# RG191-M2_Header.net
KiCad netlist of a schematic drawn in Altium Designer
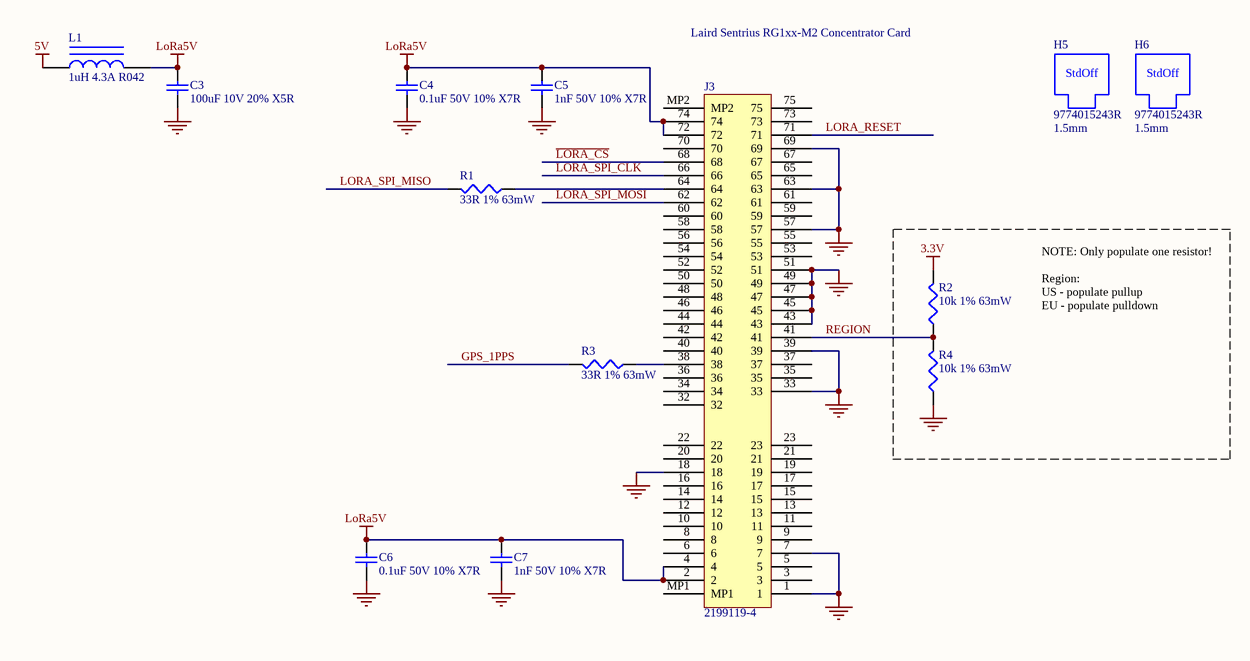
[diagram p0: RG191-M2 Header.SchDoc]

(export (version "E")
  (design (tool "Eeschema 10.0.6"))
  (components
    (comp (ref "C3")
      (value "100uF 10V 20% X5R")
      (footprint "C1210_L")
      (description "Capacitor")
      (libsource (lib "Miscellaneous Devices") (part "Cap"))
    )
    (comp (ref "C4")
      (value "0.1uF 50V 10% X7R")
      (footprint "CAPC1005L")
      (description "Capacitor")
      (libsource (lib "Miscellaneous Devices") (part "Cap"))
    )
    (comp (ref "C5")
      (value "1nF 50V 10% X7R")
      (footprint "CAPC1005L")
      (description "Capacitor")
      (libsource (lib "Miscellaneous Devices") (part "Cap"))
    )
    (comp (ref "C6")
      (value "0.1uF 50V 10% X7R")
      (footprint "CAPC1005L")
      (description "Capacitor")
      (libsource (lib "Miscellaneous Devices") (part "Cap"))
    )
    (comp (ref "C7")
      (value "1nF 50V 10% X7R")
      (footprint "CAPC1005L")
      (description "Capacitor")
      (libsource (lib "Miscellaneous Devices") (part "Cap"))
    )
    (comp (ref "H5")
      (value "9774015243R")
      (footprint "Wurth 9774015243R")
      (description "RND STANDOFF M2X0.4 STEEL")
      (fields (field (name "MANUFACTURER") "Wurth Electronics Inc") (field (name "HEIGHT") "1.5mm"))
      (libsource (lib "Latium Component Library") (part "SMD 1.5mm Spacer"))
    )
    (comp (ref "H6")
      (value "9774015243R")
      (footprint "Wurth 9774015243R")
      (description "RND STANDOFF M2X0.4 STEEL")
      (fields (field (name "MANUFACTURER") "Wurth Electronics Inc") (field (name "HEIGHT") "1.5mm"))
      (libsource (lib "Latium Component Library") (part "SMD 1.5mm Spacer"))
    )
    (comp (ref "J3")
      (value "2199119-4")
      (footprint "TE 2199119-4")
      (description "CONN FEMALE 67POS 0.020 GOLD")
      (fields (field (name "MANUFACTURER") "TE Connectivity AMP Connectors"))
      (libsource (lib "Latium Component Library") (part "TE2199119-4"))
    )
    (comp (ref "L1")
      (value "1uH 4.3A R042")
      (footprint "WE-LQS 252012")
      (description "FIXED IND 1UH 4.3A 42 MOHM SMD")
      (fields
        (field (name "MANUFACTURER PART NUMBER") "DFE252012P-1R0M=P2")
        (field (name "MANUFACTURER") "Murata Electronics")
      )
      (libsource (lib "Miscellaneous Devices") (part "Inductor Iron"))
    )
    (comp (ref "R1")
      (value "33R 1% 63mW")
      (footprint "RESC1005L")
      (description "Resistor")
      (libsource (lib "Miscellaneous Devices") (part "Res3"))
    )
    (comp (ref "R2")
      (value "10k 1% 63mW")
      (footprint "RESC1005L")
      (description "Resistor")
      (libsource (lib "Miscellaneous Devices") (part "Res3"))
    )
    (comp (ref "R3")
      (value "33R 1% 63mW")
      (footprint "RESC1005L")
      (description "Resistor")
      (libsource (lib "Miscellaneous Devices") (part "Res3"))
    )
    (comp (ref "R4")
      (value "10k 1% 63mW")
      (footprint "RESC1005L")
      (description "Resistor")
      (libsource (lib "Miscellaneous Devices") (part "Res3"))
    )
  )
  (nets
    (net (code "1") (name "/GPS_1PPS") (class "Default")
      (node (ref "R3") (pin "2") (pinfunction "2_2") (pintype "passive"))
    )
    (net (code "2") (name "/LORA_RESET") (class "Default")
      (node (ref "J3") (pin "71") (pinfunction "71_71") (pintype "passive"))
    )
    (net (code "3") (name "/LORA_SPI_CLK") (class "Default")
      (node (ref "J3") (pin "66") (pinfunction "66_66") (pintype "passive"))
    )
    (net (code "4") (name "/LORA_SPI_MISO") (class "Default")
      (node (ref "R1") (pin "2") (pinfunction "2_2") (pintype "passive"))
    )
    (net (code "5") (name "/LORA_SPI_MOSI") (class "Default")
      (node (ref "J3") (pin "62") (pinfunction "62_62") (pintype "passive"))
    )
    (net (code "6") (name "/REGION") (class "Default")
      (node (ref "J3") (pin "41") (pinfunction "41_41") (pintype "passive"))
      (node (ref "R2") (pin "1") (pinfunction "1_1") (pintype "passive"))
      (node (ref "R4") (pin "2") (pinfunction "2_2") (pintype "passive"))
    )
    (net (code "7") (name "/~{LORA_CS}") (class "Default")
      (node (ref "J3") (pin "68") (pinfunction "68_68") (pintype "passive"))
    )
    (net (code "8") (name "3.3V") (class "Default")
      (node (ref "R2") (pin "2") (pinfunction "2_2") (pintype "passive"))
    )
    (net (code "9") (name "5V") (class "Default")
      (node (ref "L1") (pin "1") (pinfunction "1_1") (pintype "passive"))
    )
    (net (code "10") (name "GND") (class "Default")
      (node (ref "C3") (pin "1") (pinfunction "1_1") (pintype "passive"))
      (node (ref "C4") (pin "2") (pinfunction "2_2") (pintype "passive"))
      (node (ref "C5") (pin "2") (pinfunction "2_2") (pintype "passive"))
      (node (ref "C6") (pin "2") (pinfunction "2_2") (pintype "passive"))
      (node (ref "C7") (pin "2") (pinfunction "2_2") (pintype "passive"))
      (node (ref "J3") (pin "1") (pinfunction "1_1") (pintype "passive"))
      (node (ref "J3") (pin "18") (pinfunction "18_18") (pintype "passive"))
      (node (ref "J3") (pin "33") (pinfunction "33_33") (pintype "passive"))
      (node (ref "J3") (pin "39") (pinfunction "39_39") (pintype "passive"))
      (node (ref "J3") (pin "43") (pinfunction "43_43") (pintype "passive"))
      (node (ref "J3") (pin "45") (pinfunction "45_45") (pintype "passive"))
      (node (ref "J3") (pin "47") (pinfunction "47_47") (pintype "passive"))
      (node (ref "J3") (pin "49") (pinfunction "49_49") (pintype "passive"))
      (node (ref "J3") (pin "51") (pinfunction "51_51") (pintype "passive"))
      (node (ref "J3") (pin "57") (pinfunction "57_57") (pintype "passive"))
      (node (ref "J3") (pin "63") (pinfunction "63_63") (pintype "passive"))
      (node (ref "J3") (pin "69") (pinfunction "69_69") (pintype "passive"))
      (node (ref "J3") (pin "7") (pinfunction "7_7") (pintype "passive"))
      (node (ref "R4") (pin "1") (pinfunction "1_1") (pintype "passive"))
    )
    (net (code "11") (name "LoRa5V") (class "Default")
      (node (ref "C3") (pin "2") (pinfunction "2_2") (pintype "passive"))
      (node (ref "C4") (pin "1") (pinfunction "1_1") (pintype "passive"))
      (node (ref "C5") (pin "1") (pinfunction "1_1") (pintype "passive"))
      (node (ref "C6") (pin "1") (pinfunction "1_1") (pintype "passive"))
      (node (ref "C7") (pin "1") (pinfunction "1_1") (pintype "passive"))
      (node (ref "J3") (pin "2") (pinfunction "2_2") (pintype "passive"))
      (node (ref "J3") (pin "4") (pinfunction "4_4") (pintype "passive"))
      (node (ref "J3") (pin "72") (pinfunction "72_72") (pintype "passive"))
      (node (ref "J3") (pin "74") (pinfunction "74_74") (pintype "passive"))
      (node (ref "L1") (pin "2") (pinfunction "2_2") (pintype "passive"))
    )
    (net (code "12") (name "Net-(J3-Pad38)") (class "Default")
      (node (ref "J3") (pin "38") (pinfunction "38_38") (pintype "passive"))
      (node (ref "R3") (pin "1") (pinfunction "1_1") (pintype "passive"))
    )
    (net (code "13") (name "Net-(J3-Pad64)") (class "Default")
      (node (ref "J3") (pin "64") (pinfunction "64_64") (pintype "passive"))
      (node (ref "R1") (pin "1") (pinfunction "1_1") (pintype "passive"))
    )
    (net (code "14") (name "unconnected-(J3-Pad3)") (class "Default")
      (node (ref "J3") (pin "3") (pinfunction "3_3") (pintype "passive"))
    )
    (net (code "15") (name "unconnected-(J3-Pad5)") (class "Default")
      (node (ref "J3") (pin "5") (pinfunction "5_5") (pintype "passive"))
    )
    (net (code "16") (name "unconnected-(J3-Pad6)") (class "Default")
      (node (ref "J3") (pin "6") (pinfunction "6_6") (pintype "passive"))
    )
    (net (code "17") (name "unconnected-(J3-Pad8)") (class "Default")
      (node (ref "J3") (pin "8") (pinfunction "8_8") (pintype "passive"))
    )
    (net (code "18") (name "unconnected-(J3-Pad9)") (class "Default")
      (node (ref "J3") (pin "9") (pinfunction "9_9") (pintype "passive"))
    )
    (net (code "19") (name "unconnected-(J3-Pad10)") (class "Default")
      (node (ref "J3") (pin "10") (pinfunction "10_10") (pintype "passive"))
    )
    (net (code "20") (name "unconnected-(J3-Pad11)") (class "Default")
      (node (ref "J3") (pin "11") (pinfunction "11_11") (pintype "passive"))
    )
    (net (code "21") (name "unconnected-(J3-Pad12)") (class "Default")
      (node (ref "J3") (pin "12") (pinfunction "12_12") (pintype "passive"))
    )
    (net (code "22") (name "unconnected-(J3-Pad13)") (class "Default")
      (node (ref "J3") (pin "13") (pinfunction "13_13") (pintype "passive"))
    )
    (net (code "23") (name "unconnected-(J3-Pad14)") (class "Default")
      (node (ref "J3") (pin "14") (pinfunction "14_14") (pintype "passive"))
    )
    (net (code "24") (name "unconnected-(J3-Pad15)") (class "Default")
      (node (ref "J3") (pin "15") (pinfunction "15_15") (pintype "passive"))
    )
    (net (code "25") (name "unconnected-(J3-Pad16)") (class "Default")
      (node (ref "J3") (pin "16") (pinfunction "16_16") (pintype "passive"))
    )
    (net (code "26") (name "unconnected-(J3-Pad17)") (class "Default")
      (node (ref "J3") (pin "17") (pinfunction "17_17") (pintype "passive"))
    )
    (net (code "27") (name "unconnected-(J3-Pad19)") (class "Default")
      (node (ref "J3") (pin "19") (pinfunction "19_19") (pintype "passive"))
    )
    (net (code "28") (name "unconnected-(J3-Pad20)") (class "Default")
      (node (ref "J3") (pin "20") (pinfunction "20_20") (pintype "passive"))
    )
    (net (code "29") (name "unconnected-(J3-Pad21)") (class "Default")
      (node (ref "J3") (pin "21") (pinfunction "21_21") (pintype "passive"))
    )
    (net (code "30") (name "unconnected-(J3-Pad22)") (class "Default")
      (node (ref "J3") (pin "22") (pinfunction "22_22") (pintype "passive"))
    )
    (net (code "31") (name "unconnected-(J3-Pad23)") (class "Default")
      (node (ref "J3") (pin "23") (pinfunction "23_23") (pintype "passive"))
    )
    (net (code "32") (name "unconnected-(J3-Pad32)") (class "Default")
      (node (ref "J3") (pin "32") (pinfunction "32_32") (pintype "passive"))
    )
    (net (code "33") (name "unconnected-(J3-Pad34)") (class "Default")
      (node (ref "J3") (pin "34") (pinfunction "34_34") (pintype "passive"))
    )
    (net (code "34") (name "unconnected-(J3-Pad35)") (class "Default")
      (node (ref "J3") (pin "35") (pinfunction "35_35") (pintype "passive"))
    )
    (net (code "35") (name "unconnected-(J3-Pad36)") (class "Default")
      (node (ref "J3") (pin "36") (pinfunction "36_36") (pintype "passive"))
    )
    (net (code "36") (name "unconnected-(J3-Pad37)") (class "Default")
      (node (ref "J3") (pin "37") (pinfunction "37_37") (pintype "passive"))
    )
    (net (code "37") (name "unconnected-(J3-Pad40)") (class "Default")
      (node (ref "J3") (pin "40") (pinfunction "40_40") (pintype "passive"))
    )
    (net (code "38") (name "unconnected-(J3-Pad42)") (class "Default")
      (node (ref "J3") (pin "42") (pinfunction "42_42") (pintype "passive"))
    )
    (net (code "39") (name "unconnected-(J3-Pad44)") (class "Default")
      (node (ref "J3") (pin "44") (pinfunction "44_44") (pintype "passive"))
    )
    (net (code "40") (name "unconnected-(J3-Pad46)") (class "Default")
      (node (ref "J3") (pin "46") (pinfunction "46_46") (pintype "passive"))
    )
    (net (code "41") (name "unconnected-(J3-Pad48)") (class "Default")
      (node (ref "J3") (pin "48") (pinfunction "48_48") (pintype "passive"))
    )
    (net (code "42") (name "unconnected-(J3-Pad50)") (class "Default")
      (node (ref "J3") (pin "50") (pinfunction "50_50") (pintype "passive"))
    )
    (net (code "43") (name "unconnected-(J3-Pad52)") (class "Default")
      (node (ref "J3") (pin "52") (pinfunction "52_52") (pintype "passive"))
    )
    (net (code "44") (name "unconnected-(J3-Pad53)") (class "Default")
      (node (ref "J3") (pin "53") (pinfunction "53_53") (pintype "passive"))
    )
    (net (code "45") (name "unconnected-(J3-Pad54)") (class "Default")
      (node (ref "J3") (pin "54") (pinfunction "54_54") (pintype "passive"))
    )
    (net (code "46") (name "unconnected-(J3-Pad55)") (class "Default")
      (node (ref "J3") (pin "55") (pinfunction "55_55") (pintype "passive"))
    )
    (net (code "47") (name "unconnected-(J3-Pad56)") (class "Default")
      (node (ref "J3") (pin "56") (pinfunction "56_56") (pintype "passive"))
    )
    (net (code "48") (name "unconnected-(J3-Pad58)") (class "Default")
      (node (ref "J3") (pin "58") (pinfunction "58_58") (pintype "passive"))
    )
    (net (code "49") (name "unconnected-(J3-Pad59)") (class "Default")
      (node (ref "J3") (pin "59") (pinfunction "59_59") (pintype "passive"))
    )
    (net (code "50") (name "unconnected-(J3-Pad60)") (class "Default")
      (node (ref "J3") (pin "60") (pinfunction "60_60") (pintype "passive"))
    )
    (net (code "51") (name "unconnected-(J3-Pad61)") (class "Default")
      (node (ref "J3") (pin "61") (pinfunction "61_61") (pintype "passive"))
    )
    (net (code "52") (name "unconnected-(J3-Pad65)") (class "Default")
      (node (ref "J3") (pin "65") (pinfunction "65_65") (pintype "passive"))
    )
    (net (code "53") (name "unconnected-(J3-Pad67)") (class "Default")
      (node (ref "J3") (pin "67") (pinfunction "67_67") (pintype "passive"))
    )
    (net (code "54") (name "unconnected-(J3-Pad70)") (class "Default")
      (node (ref "J3") (pin "70") (pinfunction "70_70") (pintype "passive"))
    )
    (net (code "55") (name "unconnected-(J3-Pad73)") (class "Default")
      (node (ref "J3") (pin "73") (pinfunction "73_73") (pintype "passive"))
    )
    (net (code "56") (name "unconnected-(J3-Pad75)") (class "Default")
      (node (ref "J3") (pin "75") (pinfunction "75_75") (pintype "passive"))
    )
    (net (code "57") (name "unconnected-(J3-PadMP1)") (class "Default")
      (node (ref "J3") (pin "MP1") (pinfunction "MP1_MP1") (pintype "passive"))
    )
    (net (code "58") (name "unconnected-(J3-PadMP2)") (class "Default")
      (node (ref "J3") (pin "MP2") (pinfunction "MP2_MP2") (pintype "passive"))
    )
  )
)
